# rp2040_core.net
KiCad netlist of a schematic drawn in Altium Designer
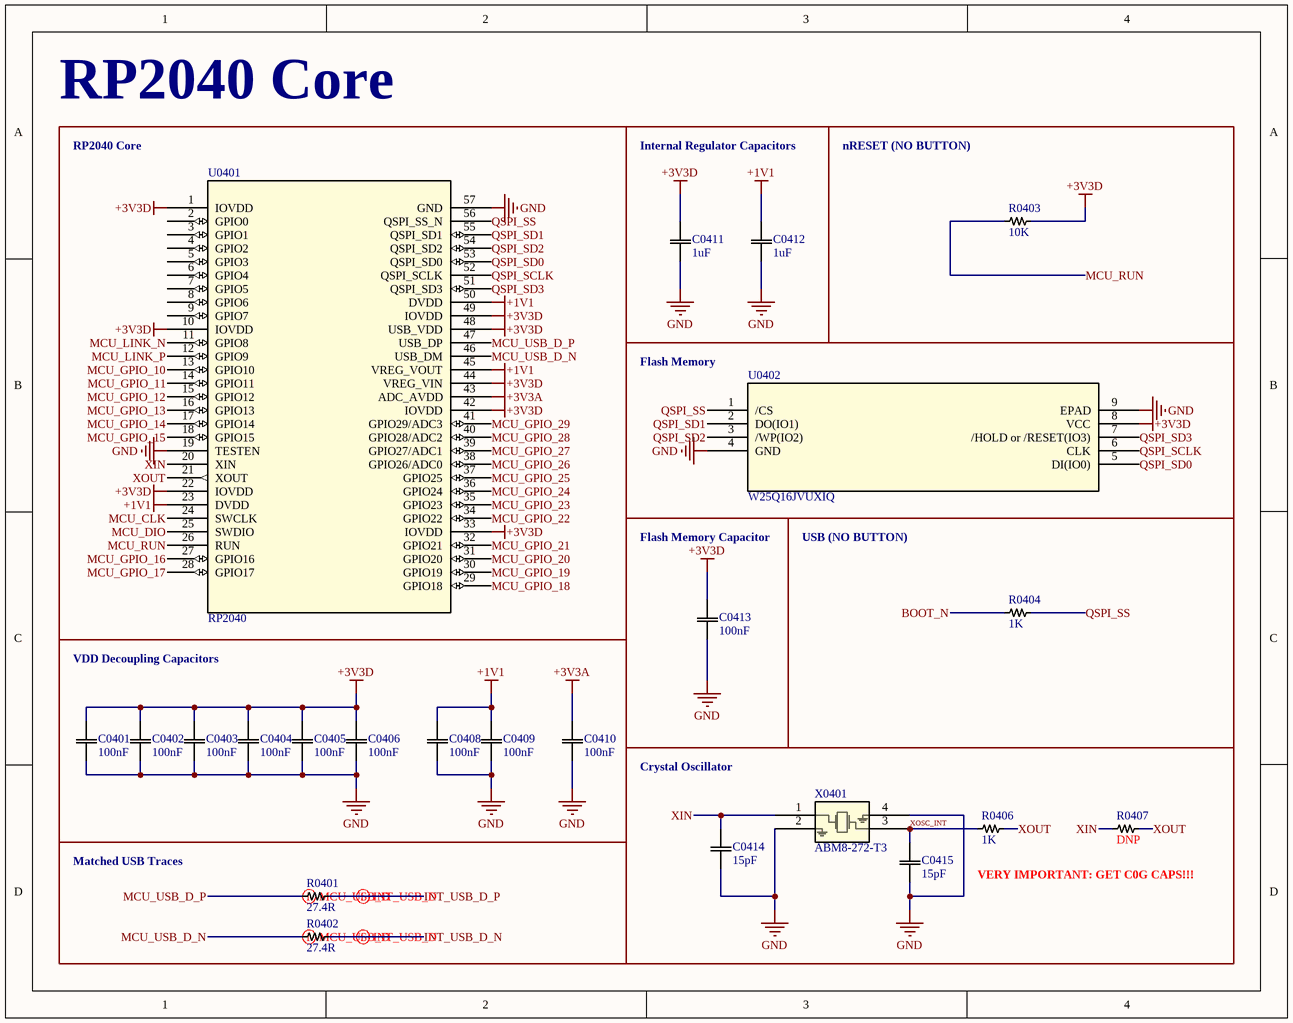
[diagram p0: rp2040_core.SchDoc]

(export (version "E")
  (design (tool "Eeschema 10.0.6"))
  (components
    (comp (ref "C0401")
      (value "100nF")
      (footprint "CAPC10555_55N_KEM")
      (description "SMD Comm X7R, Ceramic, SMD, MLCC, Temperature Stable, 0402")
      (fields
        (field (name "MANUFACTURER_PART_NUMBER") "C0402C104K4RACTU")
        (field (name "COPYRIGHT") "Copyright (C) 2025 Ultra Librarian. All rights reserved.")
      )
      (libsource (lib "SplitHE_Int") (part "C0402"))
    )
    (comp (ref "C0402")
      (value "100nF")
      (footprint "CAPC10555_55N_KEM")
      (description "SMD Comm X7R, Ceramic, SMD, MLCC, Temperature Stable, 0402")
      (fields
        (field (name "MANUFACTURER_PART_NUMBER") "C0402C104K4RACTU")
        (field (name "COPYRIGHT") "Copyright (C) 2025 Ultra Librarian. All rights reserved.")
      )
      (libsource (lib "SplitHE_Int") (part "C0402"))
    )
    (comp (ref "C0403")
      (value "100nF")
      (footprint "CAPC10555_55N_KEM")
      (description "SMD Comm X7R, Ceramic, SMD, MLCC, Temperature Stable, 0402")
      (fields
        (field (name "MANUFACTURER_PART_NUMBER") "C0402C104K4RACTU")
        (field (name "COPYRIGHT") "Copyright (C) 2025 Ultra Librarian. All rights reserved.")
      )
      (libsource (lib "SplitHE_Int") (part "C0402"))
    )
    (comp (ref "C0404")
      (value "100nF")
      (footprint "CAPC10555_55N_KEM")
      (description "SMD Comm X7R, Ceramic, SMD, MLCC, Temperature Stable, 0402")
      (fields
        (field (name "MANUFACTURER_PART_NUMBER") "C0402C104K4RACTU")
        (field (name "COPYRIGHT") "Copyright (C) 2025 Ultra Librarian. All rights reserved.")
      )
      (libsource (lib "SplitHE_Int") (part "C0402"))
    )
    (comp (ref "C0405")
      (value "100nF")
      (footprint "CAPC10555_55N_KEM")
      (description "SMD Comm X7R, Ceramic, SMD, MLCC, Temperature Stable, 0402")
      (fields
        (field (name "MANUFACTURER_PART_NUMBER") "C0402C104K4RACTU")
        (field (name "COPYRIGHT") "Copyright (C) 2025 Ultra Librarian. All rights reserved.")
      )
      (libsource (lib "SplitHE_Int") (part "C0402"))
    )
    (comp (ref "C0406")
      (value "100nF")
      (footprint "CAPC10555_55N_KEM")
      (description "SMD Comm X7R, Ceramic, SMD, MLCC, Temperature Stable, 0402")
      (fields
        (field (name "MANUFACTURER_PART_NUMBER") "C0402C104K4RACTU")
        (field (name "COPYRIGHT") "Copyright (C) 2025 Ultra Librarian. All rights reserved.")
      )
      (libsource (lib "SplitHE_Int") (part "C0402"))
    )
    (comp (ref "C0408")
      (value "100nF")
      (footprint "CAPC10555_55N_KEM")
      (description "SMD Comm X7R, Ceramic, SMD, MLCC, Temperature Stable, 0402")
      (fields
        (field (name "MANUFACTURER_PART_NUMBER") "C0402C104K4RACTU")
        (field (name "COPYRIGHT") "Copyright (C) 2025 Ultra Librarian. All rights reserved.")
      )
      (libsource (lib "SplitHE_Int") (part "C0402"))
    )
    (comp (ref "C0409")
      (value "100nF")
      (footprint "CAPC10555_55N_KEM")
      (description "SMD Comm X7R, Ceramic, SMD, MLCC, Temperature Stable, 0402")
      (fields
        (field (name "MANUFACTURER_PART_NUMBER") "C0402C104K4RACTU")
        (field (name "COPYRIGHT") "Copyright (C) 2025 Ultra Librarian. All rights reserved.")
      )
      (libsource (lib "SplitHE_Int") (part "C0402"))
    )
    (comp (ref "C0410")
      (value "100nF")
      (footprint "CAPC10555_55N_KEM")
      (description "SMD Comm X7R, Ceramic, SMD, MLCC, Temperature Stable, 0402")
      (fields
        (field (name "MANUFACTURER_PART_NUMBER") "C0402C104K4RACTU")
        (field (name "COPYRIGHT") "Copyright (C) 2025 Ultra Librarian. All rights reserved.")
      )
      (libsource (lib "SplitHE_Int") (part "C0402"))
    )
    (comp (ref "C0411")
      (value "1uF")
      (footprint "CAPC10555_55N_KEM")
      (description "SMD Comm X7R, Ceramic, SMD, MLCC, Temperature Stable, 0402")
      (fields
        (field (name "MANUFACTURER_PART_NUMBER") "C0402C104K4RACTU")
        (field (name "COPYRIGHT") "Copyright (C) 2025 Ultra Librarian. All rights reserved.")
      )
      (libsource (lib "SplitHE_Int") (part "C0402"))
    )
    (comp (ref "C0412")
      (value "1uF")
      (footprint "CAPC10555_55N_KEM")
      (description "SMD Comm X7R, Ceramic, SMD, MLCC, Temperature Stable, 0402")
      (fields
        (field (name "MANUFACTURER_PART_NUMBER") "C0402C104K4RACTU")
        (field (name "COPYRIGHT") "Copyright (C) 2025 Ultra Librarian. All rights reserved.")
      )
      (libsource (lib "SplitHE_Int") (part "C0402"))
    )
    (comp (ref "C0413")
      (value "100nF")
      (footprint "CAPC10555_55N_KEM")
      (description "SMD Comm X7R, Ceramic, SMD, MLCC, Temperature Stable, 0402")
      (fields
        (field (name "MANUFACTURER_PART_NUMBER") "C0402C104K4RACTU")
        (field (name "COPYRIGHT") "Copyright (C) 2025 Ultra Librarian. All rights reserved.")
      )
      (libsource (lib "SplitHE_Int") (part "C0402"))
    )
    (comp (ref "C0414")
      (value "15pF")
      (footprint "CAPC10555_55N_KEM")
      (description "SMD Comm X7R, Ceramic, SMD, MLCC, Temperature Stable, 0402")
      (fields
        (field (name "MANUFACTURER_PART_NUMBER") "C0402C104K4RACTU")
        (field (name "COPYRIGHT") "Copyright (C) 2025 Ultra Librarian. All rights reserved.")
      )
      (libsource (lib "SplitHE_Int") (part "C0402"))
    )
    (comp (ref "C0415")
      (value "15pF")
      (footprint "CAPC10555_55N_KEM")
      (description "SMD Comm X7R, Ceramic, SMD, MLCC, Temperature Stable, 0402")
      (fields
        (field (name "MANUFACTURER_PART_NUMBER") "C0402C104K4RACTU")
        (field (name "COPYRIGHT") "Copyright (C) 2025 Ultra Librarian. All rights reserved.")
      )
      (libsource (lib "SplitHE_Int") (part "C0402"))
    )
    (comp (ref "R0401")
      (value "27.4R")
      (footprint "RES0402_CPF_TYCO_TYC")
      (description "CPF 0402 RL")
      (fields
        (field (name "MANUFACTURER_PART_NUMBER") "CPF0402B33RE1")
        (field (name "COPYRIGHT") "Copyright (C) 2025 Ultra Librarian. All rights reserved.")
      )
      (libsource (lib "SplitHE_Int") (part "R0402"))
    )
    (comp (ref "R0402")
      (value "27.4R")
      (footprint "RES0402_CPF_TYCO_TYC")
      (description "CPF 0402 RL")
      (fields
        (field (name "MANUFACTURER_PART_NUMBER") "CPF0402B33RE1")
        (field (name "COPYRIGHT") "Copyright (C) 2025 Ultra Librarian. All rights reserved.")
      )
      (libsource (lib "SplitHE_Int") (part "R0402"))
    )
    (comp (ref "R0403")
      (value "10K")
      (footprint "RES0402_CPF_TYCO_TYC")
      (description "CPF 0402 RL")
      (fields
        (field (name "MANUFACTURER_PART_NUMBER") "CPF0402B33RE1")
        (field (name "COPYRIGHT") "Copyright (C) 2025 Ultra Librarian. All rights reserved.")
      )
      (libsource (lib "SplitHE_Int") (part "R0402"))
    )
    (comp (ref "R0404")
      (value "1K")
      (footprint "RES0402_CPF_TYCO_TYC")
      (description "CPF 0402 RL")
      (fields
        (field (name "MANUFACTURER_PART_NUMBER") "CPF0402B33RE1")
        (field (name "COPYRIGHT") "Copyright (C) 2025 Ultra Librarian. All rights reserved.")
      )
      (libsource (lib "SplitHE_Int") (part "R0402"))
    )
    (comp (ref "R0406")
      (value "1K")
      (footprint "RES0402_CPF_TYCO_TYC")
      (description "CPF 0402 RL")
      (fields
        (field (name "MANUFACTURER_PART_NUMBER") "CPF0402B33RE1")
        (field (name "COPYRIGHT") "Copyright (C) 2025 Ultra Librarian. All rights reserved.")
      )
      (libsource (lib "SplitHE_Int") (part "R0402"))
    )
    (comp (ref "R0407")
      (value "DNP")
      (footprint "RES0402_CPF_TYCO_TYC")
      (description "CPF 0402 RL")
      (fields
        (field (name "MANUFACTURER_PART_NUMBER") "CPF0402B33RE1")
        (field (name "COPYRIGHT") "Copyright (C) 2025 Ultra Librarian. All rights reserved.")
      )
      (libsource (lib "SplitHE_Int") (part "R0402"))
    )
    (comp (ref "U0401")
      (value "RP2040")
      (footprint "IC57_RP2040")
      (description "No Description Available")
      (fields (field (name "COPYRIGHT") "Copyright (C) 2025 Ultra Librarian. All rights reserved."))
      (libsource (lib "SplitHE_Int") (part "RP2040"))
    )
    (comp (ref "U0402")
      (value "W25Q16JVUXIQ")
      (footprint "W25Q16JVUXIQ_WIN")
      (description "No Description Available")
      (fields (field (name "COPYRIGHT") "Copyright (C) 2025 Ultra Librarian. All rights reserved."))
      (libsource (lib "W25Q16JVUXIQ") (part "W25Q16JVUXIQ"))
    )
    (comp (ref "X0401")
      (value "ABM8-272-T3")
      (footprint "ABM8-272-T3_ABR")
      (description "No Description Available")
      (fields (field (name "COPYRIGHT") "Copyright (C) 2025 Ultra Librarian. All rights reserved."))
      (libsource (lib "ABM8-272-T3") (part "ABM8-272-T3"))
    )
  )
  (nets
    (net (code "1") (name "+1V1") (class "Default")
      (node (ref "C0408") (pin "2") (pinfunction "2_2") (pintype "passive"))
      (node (ref "C0409") (pin "2") (pinfunction "2_2") (pintype "passive"))
      (node (ref "C0412") (pin "2") (pinfunction "2_2") (pintype "passive"))
      (node (ref "U0401") (pin "23") (pinfunction "DVDD_23") (pintype "power_in"))
      (node (ref "U0401") (pin "45") (pinfunction "VREG_VOUT_45") (pintype "power_in"))
      (node (ref "U0401") (pin "50") (pinfunction "DVDD_50") (pintype "power_in"))
    )
    (net (code "2") (name "+3V3A") (class "Default")
      (node (ref "C0410") (pin "2") (pinfunction "2_2") (pintype "passive"))
      (node (ref "U0401") (pin "43") (pinfunction "ADC_AVDD_43") (pintype "power_in"))
    )
    (net (code "3") (name "+3V3D") (class "Default")
      (node (ref "C0401") (pin "2") (pinfunction "2_2") (pintype "passive"))
      (node (ref "C0402") (pin "2") (pinfunction "2_2") (pintype "passive"))
      (node (ref "C0403") (pin "2") (pinfunction "2_2") (pintype "passive"))
      (node (ref "C0404") (pin "2") (pinfunction "2_2") (pintype "passive"))
      (node (ref "C0405") (pin "2") (pinfunction "2_2") (pintype "passive"))
      (node (ref "C0406") (pin "2") (pinfunction "2_2") (pintype "passive"))
      (node (ref "C0411") (pin "2") (pinfunction "2_2") (pintype "passive"))
      (node (ref "C0413") (pin "2") (pinfunction "2_2") (pintype "passive"))
      (node (ref "R0403") (pin "1") (pinfunction "1_1") (pintype "passive"))
      (node (ref "U0401") (pin "1") (pinfunction "IOVDD_1") (pintype "power_in"))
      (node (ref "U0401") (pin "10") (pinfunction "IOVDD_10") (pintype "power_in"))
      (node (ref "U0401") (pin "22") (pinfunction "IOVDD_22") (pintype "power_in"))
      (node (ref "U0401") (pin "33") (pinfunction "IOVDD_33") (pintype "power_in"))
      (node (ref "U0401") (pin "42") (pinfunction "IOVDD_42") (pintype "power_in"))
      (node (ref "U0401") (pin "44") (pinfunction "VREG_VIN_44") (pintype "passive"))
      (node (ref "U0401") (pin "48") (pinfunction "USB_VDD_48") (pintype "power_in"))
      (node (ref "U0401") (pin "49") (pinfunction "IOVDD_49") (pintype "power_in"))
      (node (ref "U0402") (pin "8") (pinfunction "VCC_8") (pintype "passive"))
    )
    (net (code "4") (name "/BOOT_N") (class "Default")
      (node (ref "R0404") (pin "2") (pinfunction "2_2") (pintype "passive"))
    )
    (net (code "5") (name "/INT_USB_D_N") (class "Default")
      (node (ref "R0402") (pin "1") (pinfunction "1_1") (pintype "passive"))
    )
    (net (code "6") (name "/INT_USB_D_P") (class "Default")
      (node (ref "R0401") (pin "1") (pinfunction "1_1") (pintype "passive"))
    )
    (net (code "7") (name "/MCU_CLK") (class "Default")
      (node (ref "U0401") (pin "24") (pinfunction "SWCLK_24") (pintype "passive"))
    )
    (net (code "8") (name "/MCU_DIO") (class "Default")
      (node (ref "U0401") (pin "25") (pinfunction "SWDIO_25") (pintype "passive"))
    )
    (net (code "9") (name "/MCU_GPIO_10") (class "Default")
      (node (ref "U0401") (pin "13") (pinfunction "GPIO10_13") (pintype "bidirectional"))
    )
    (net (code "10") (name "/MCU_GPIO_11") (class "Default")
      (node (ref "U0401") (pin "14") (pinfunction "GPIO11_14") (pintype "bidirectional"))
    )
    (net (code "11") (name "/MCU_GPIO_12") (class "Default")
      (node (ref "U0401") (pin "15") (pinfunction "GPIO12_15") (pintype "bidirectional"))
    )
    (net (code "12") (name "/MCU_GPIO_13") (class "Default")
      (node (ref "U0401") (pin "16") (pinfunction "GPIO13_16") (pintype "bidirectional"))
    )
    (net (code "13") (name "/MCU_GPIO_14") (class "Default")
      (node (ref "U0401") (pin "17") (pinfunction "GPIO14_17") (pintype "bidirectional"))
    )
    (net (code "14") (name "/MCU_GPIO_15") (class "Default")
      (node (ref "U0401") (pin "18") (pinfunction "GPIO15_18") (pintype "bidirectional"))
    )
    (net (code "15") (name "/MCU_GPIO_16") (class "Default")
      (node (ref "U0401") (pin "27") (pinfunction "GPIO16_27") (pintype "bidirectional"))
    )
    (net (code "16") (name "/MCU_GPIO_17") (class "Default")
      (node (ref "U0401") (pin "28") (pinfunction "GPIO17_28") (pintype "bidirectional"))
    )
    (net (code "17") (name "/MCU_GPIO_18") (class "Default")
      (node (ref "U0401") (pin "29") (pinfunction "GPIO18_29") (pintype "bidirectional"))
    )
    (net (code "18") (name "/MCU_GPIO_19") (class "Default")
      (node (ref "U0401") (pin "30") (pinfunction "GPIO19_30") (pintype "bidirectional"))
    )
    (net (code "19") (name "/MCU_GPIO_20") (class "Default")
      (node (ref "U0401") (pin "31") (pinfunction "GPIO20_31") (pintype "bidirectional"))
    )
    (net (code "20") (name "/MCU_GPIO_21") (class "Default")
      (node (ref "U0401") (pin "32") (pinfunction "GPIO21_32") (pintype "bidirectional"))
    )
    (net (code "21") (name "/MCU_GPIO_22") (class "Default")
      (node (ref "U0401") (pin "34") (pinfunction "GPIO22_34") (pintype "bidirectional"))
    )
    (net (code "22") (name "/MCU_GPIO_23") (class "Default")
      (node (ref "U0401") (pin "35") (pinfunction "GPIO23_35") (pintype "bidirectional"))
    )
    (net (code "23") (name "/MCU_GPIO_24") (class "Default")
      (node (ref "U0401") (pin "36") (pinfunction "GPIO24_36") (pintype "bidirectional"))
    )
    (net (code "24") (name "/MCU_GPIO_25") (class "Default")
      (node (ref "U0401") (pin "37") (pinfunction "GPIO25_37") (pintype "bidirectional"))
    )
    (net (code "25") (name "/MCU_GPIO_26") (class "Default")
      (node (ref "U0401") (pin "38") (pinfunction "GPIO26/ADC0_38") (pintype "bidirectional"))
    )
    (net (code "26") (name "/MCU_GPIO_27") (class "Default")
      (node (ref "U0401") (pin "39") (pinfunction "GPIO27/ADC1_39") (pintype "bidirectional"))
    )
    (net (code "27") (name "/MCU_GPIO_28") (class "Default")
      (node (ref "U0401") (pin "40") (pinfunction "GPIO28/ADC2_40") (pintype "bidirectional"))
    )
    (net (code "28") (name "/MCU_GPIO_29") (class "Default")
      (node (ref "U0401") (pin "41") (pinfunction "GPIO29/ADC3_41") (pintype "bidirectional"))
    )
    (net (code "29") (name "/MCU_LINK_N") (class "Default")
      (node (ref "U0401") (pin "11") (pinfunction "GPIO8_11") (pintype "bidirectional"))
    )
    (net (code "30") (name "/MCU_LINK_P") (class "Default")
      (node (ref "U0401") (pin "12") (pinfunction "GPIO9_12") (pintype "bidirectional"))
    )
    (net (code "31") (name "/MCU_RUN") (class "Default")
      (node (ref "R0403") (pin "2") (pinfunction "2_2") (pintype "passive"))
      (node (ref "U0401") (pin "26") (pinfunction "RUN_26") (pintype "passive"))
    )
    (net (code "32") (name "/MCU_USB_D_N") (class "Default")
      (node (ref "R0402") (pin "2") (pinfunction "2_2") (pintype "passive"))
      (node (ref "U0401") (pin "46") (pinfunction "USB_DM_46") (pintype "passive"))
    )
    (net (code "33") (name "/MCU_USB_D_P") (class "Default")
      (node (ref "R0401") (pin "2") (pinfunction "2_2") (pintype "passive"))
      (node (ref "U0401") (pin "47") (pinfunction "USB_DP_47") (pintype "passive"))
    )
    (net (code "34") (name "/QSPI_SCLK") (class "Default")
      (node (ref "U0401") (pin "52") (pinfunction "QSPI_SCLK_52") (pintype "passive"))
      (node (ref "U0402") (pin "6") (pinfunction "CLK_6") (pintype "passive"))
    )
    (net (code "35") (name "/QSPI_SD0") (class "Default")
      (node (ref "U0401") (pin "53") (pinfunction "QSPI_SD0_53") (pintype "bidirectional"))
      (node (ref "U0402") (pin "5") (pinfunction "DI(IO0)_5") (pintype "passive"))
    )
    (net (code "36") (name "/QSPI_SD1") (class "Default")
      (node (ref "U0401") (pin "55") (pinfunction "QSPI_SD1_55") (pintype "bidirectional"))
      (node (ref "U0402") (pin "2") (pinfunction "DO(IO1)_2") (pintype "passive"))
    )
    (net (code "37") (name "/QSPI_SD2") (class "Default")
      (node (ref "U0401") (pin "54") (pinfunction "QSPI_SD2_54") (pintype "bidirectional"))
      (node (ref "U0402") (pin "3") (pinfunction "/WP(IO2)_3") (pintype "passive"))
    )
    (net (code "38") (name "/QSPI_SD3") (class "Default")
      (node (ref "U0401") (pin "51") (pinfunction "QSPI_SD3_51") (pintype "bidirectional"))
      (node (ref "U0402") (pin "7") (pinfunction "/HOLD_or_/RESET(IO3)_7") (pintype "passive"))
    )
    (net (code "39") (name "/QSPI_SS") (class "Default")
      (node (ref "R0404") (pin "1") (pinfunction "1_1") (pintype "passive"))
      (node (ref "U0401") (pin "56") (pinfunction "QSPI_SS_N_56") (pintype "passive"))
      (node (ref "U0402") (pin "1") (pinfunction "/CS_1") (pintype "passive"))
    )
    (net (code "40") (name "/XIN") (class "Default")
      (node (ref "C0414") (pin "1") (pinfunction "1_1") (pintype "passive"))
      (node (ref "R0407") (pin "1") (pinfunction "1_1") (pintype "passive"))
      (node (ref "U0401") (pin "20") (pinfunction "XIN_20") (pintype "passive"))
      (node (ref "X0401") (pin "1") (pinfunction "1_1") (pintype "passive"))
    )
    (net (code "41") (name "/XOSC_INT") (class "Default")
      (node (ref "C0415") (pin "2") (pinfunction "2_2") (pintype "passive"))
      (node (ref "R0406") (pin "1") (pinfunction "1_1") (pintype "passive"))
      (node (ref "X0401") (pin "3") (pinfunction "3_3") (pintype "passive"))
    )
    (net (code "42") (name "/XOUT") (class "Default")
      (node (ref "R0406") (pin "2") (pinfunction "2_2") (pintype "passive"))
      (node (ref "R0407") (pin "2") (pinfunction "2_2") (pintype "passive"))
      (node (ref "U0401") (pin "21") (pinfunction "XOUT_21") (pintype "output"))
    )
    (net (code "43") (name "GND") (class "Default")
      (node (ref "C0401") (pin "1") (pinfunction "1_1") (pintype "passive"))
      (node (ref "C0402") (pin "1") (pinfunction "1_1") (pintype "passive"))
      (node (ref "C0403") (pin "1") (pinfunction "1_1") (pintype "passive"))
      (node (ref "C0404") (pin "1") (pinfunction "1_1") (pintype "passive"))
      (node (ref "C0405") (pin "1") (pinfunction "1_1") (pintype "passive"))
      (node (ref "C0406") (pin "1") (pinfunction "1_1") (pintype "passive"))
      (node (ref "C0408") (pin "1") (pinfunction "1_1") (pintype "passive"))
      (node (ref "C0409") (pin "1") (pinfunction "1_1") (pintype "passive"))
      (node (ref "C0410") (pin "1") (pinfunction "1_1") (pintype "passive"))
      (node (ref "C0411") (pin "1") (pinfunction "1_1") (pintype "passive"))
      (node (ref "C0412") (pin "1") (pinfunction "1_1") (pintype "passive"))
      (node (ref "C0413") (pin "1") (pinfunction "1_1") (pintype "passive"))
      (node (ref "C0414") (pin "2") (pinfunction "2_2") (pintype "passive"))
      (node (ref "C0415") (pin "1") (pinfunction "1_1") (pintype "passive"))
      (node (ref "U0401") (pin "19") (pinfunction "TESTEN_19") (pintype "passive"))
      (node (ref "U0401") (pin "57") (pinfunction "GND_57") (pintype "power_in"))
      (node (ref "U0402") (pin "4") (pinfunction "GND_4") (pintype "passive"))
      (node (ref "U0402") (pin "9") (pinfunction "EPAD_9") (pintype "passive"))
      (node (ref "X0401") (pin "2") (pinfunction "2_2") (pintype "passive"))
      (node (ref "X0401") (pin "4") (pinfunction "4_4") (pintype "passive"))
    )
    (net (code "44") (name "unconnected-(U0401-GPIO0-Pad2)") (class "Default")
      (node (ref "U0401") (pin "2") (pinfunction "GPIO0_2") (pintype "bidirectional"))
    )
    (net (code "45") (name "unconnected-(U0401-GPIO1-Pad3)") (class "Default")
      (node (ref "U0401") (pin "3") (pinfunction "GPIO1_3") (pintype "bidirectional"))
    )
    (net (code "46") (name "unconnected-(U0401-GPIO2-Pad4)") (class "Default")
      (node (ref "U0401") (pin "4") (pinfunction "GPIO2_4") (pintype "bidirectional"))
    )
    (net (code "47") (name "unconnected-(U0401-GPIO3-Pad5)") (class "Default")
      (node (ref "U0401") (pin "5") (pinfunction "GPIO3_5") (pintype "bidirectional"))
    )
    (net (code "48") (name "unconnected-(U0401-GPIO4-Pad6)") (class "Default")
      (node (ref "U0401") (pin "6") (pinfunction "GPIO4_6") (pintype "bidirectional"))
    )
    (net (code "49") (name "unconnected-(U0401-GPIO5-Pad7)") (class "Default")
      (node (ref "U0401") (pin "7") (pinfunction "GPIO5_7") (pintype "bidirectional"))
    )
    (net (code "50") (name "unconnected-(U0401-GPIO6-Pad8)") (class "Default")
      (node (ref "U0401") (pin "8") (pinfunction "GPIO6_8") (pintype "bidirectional"))
    )
    (net (code "51") (name "unconnected-(U0401-GPIO7-Pad9)") (class "Default")
      (node (ref "U0401") (pin "9") (pinfunction "GPIO7_9") (pintype "bidirectional"))
    )
  )
)
